# acoustic_1_1.net
KiCad netlist of a schematic drawn in EAGLE
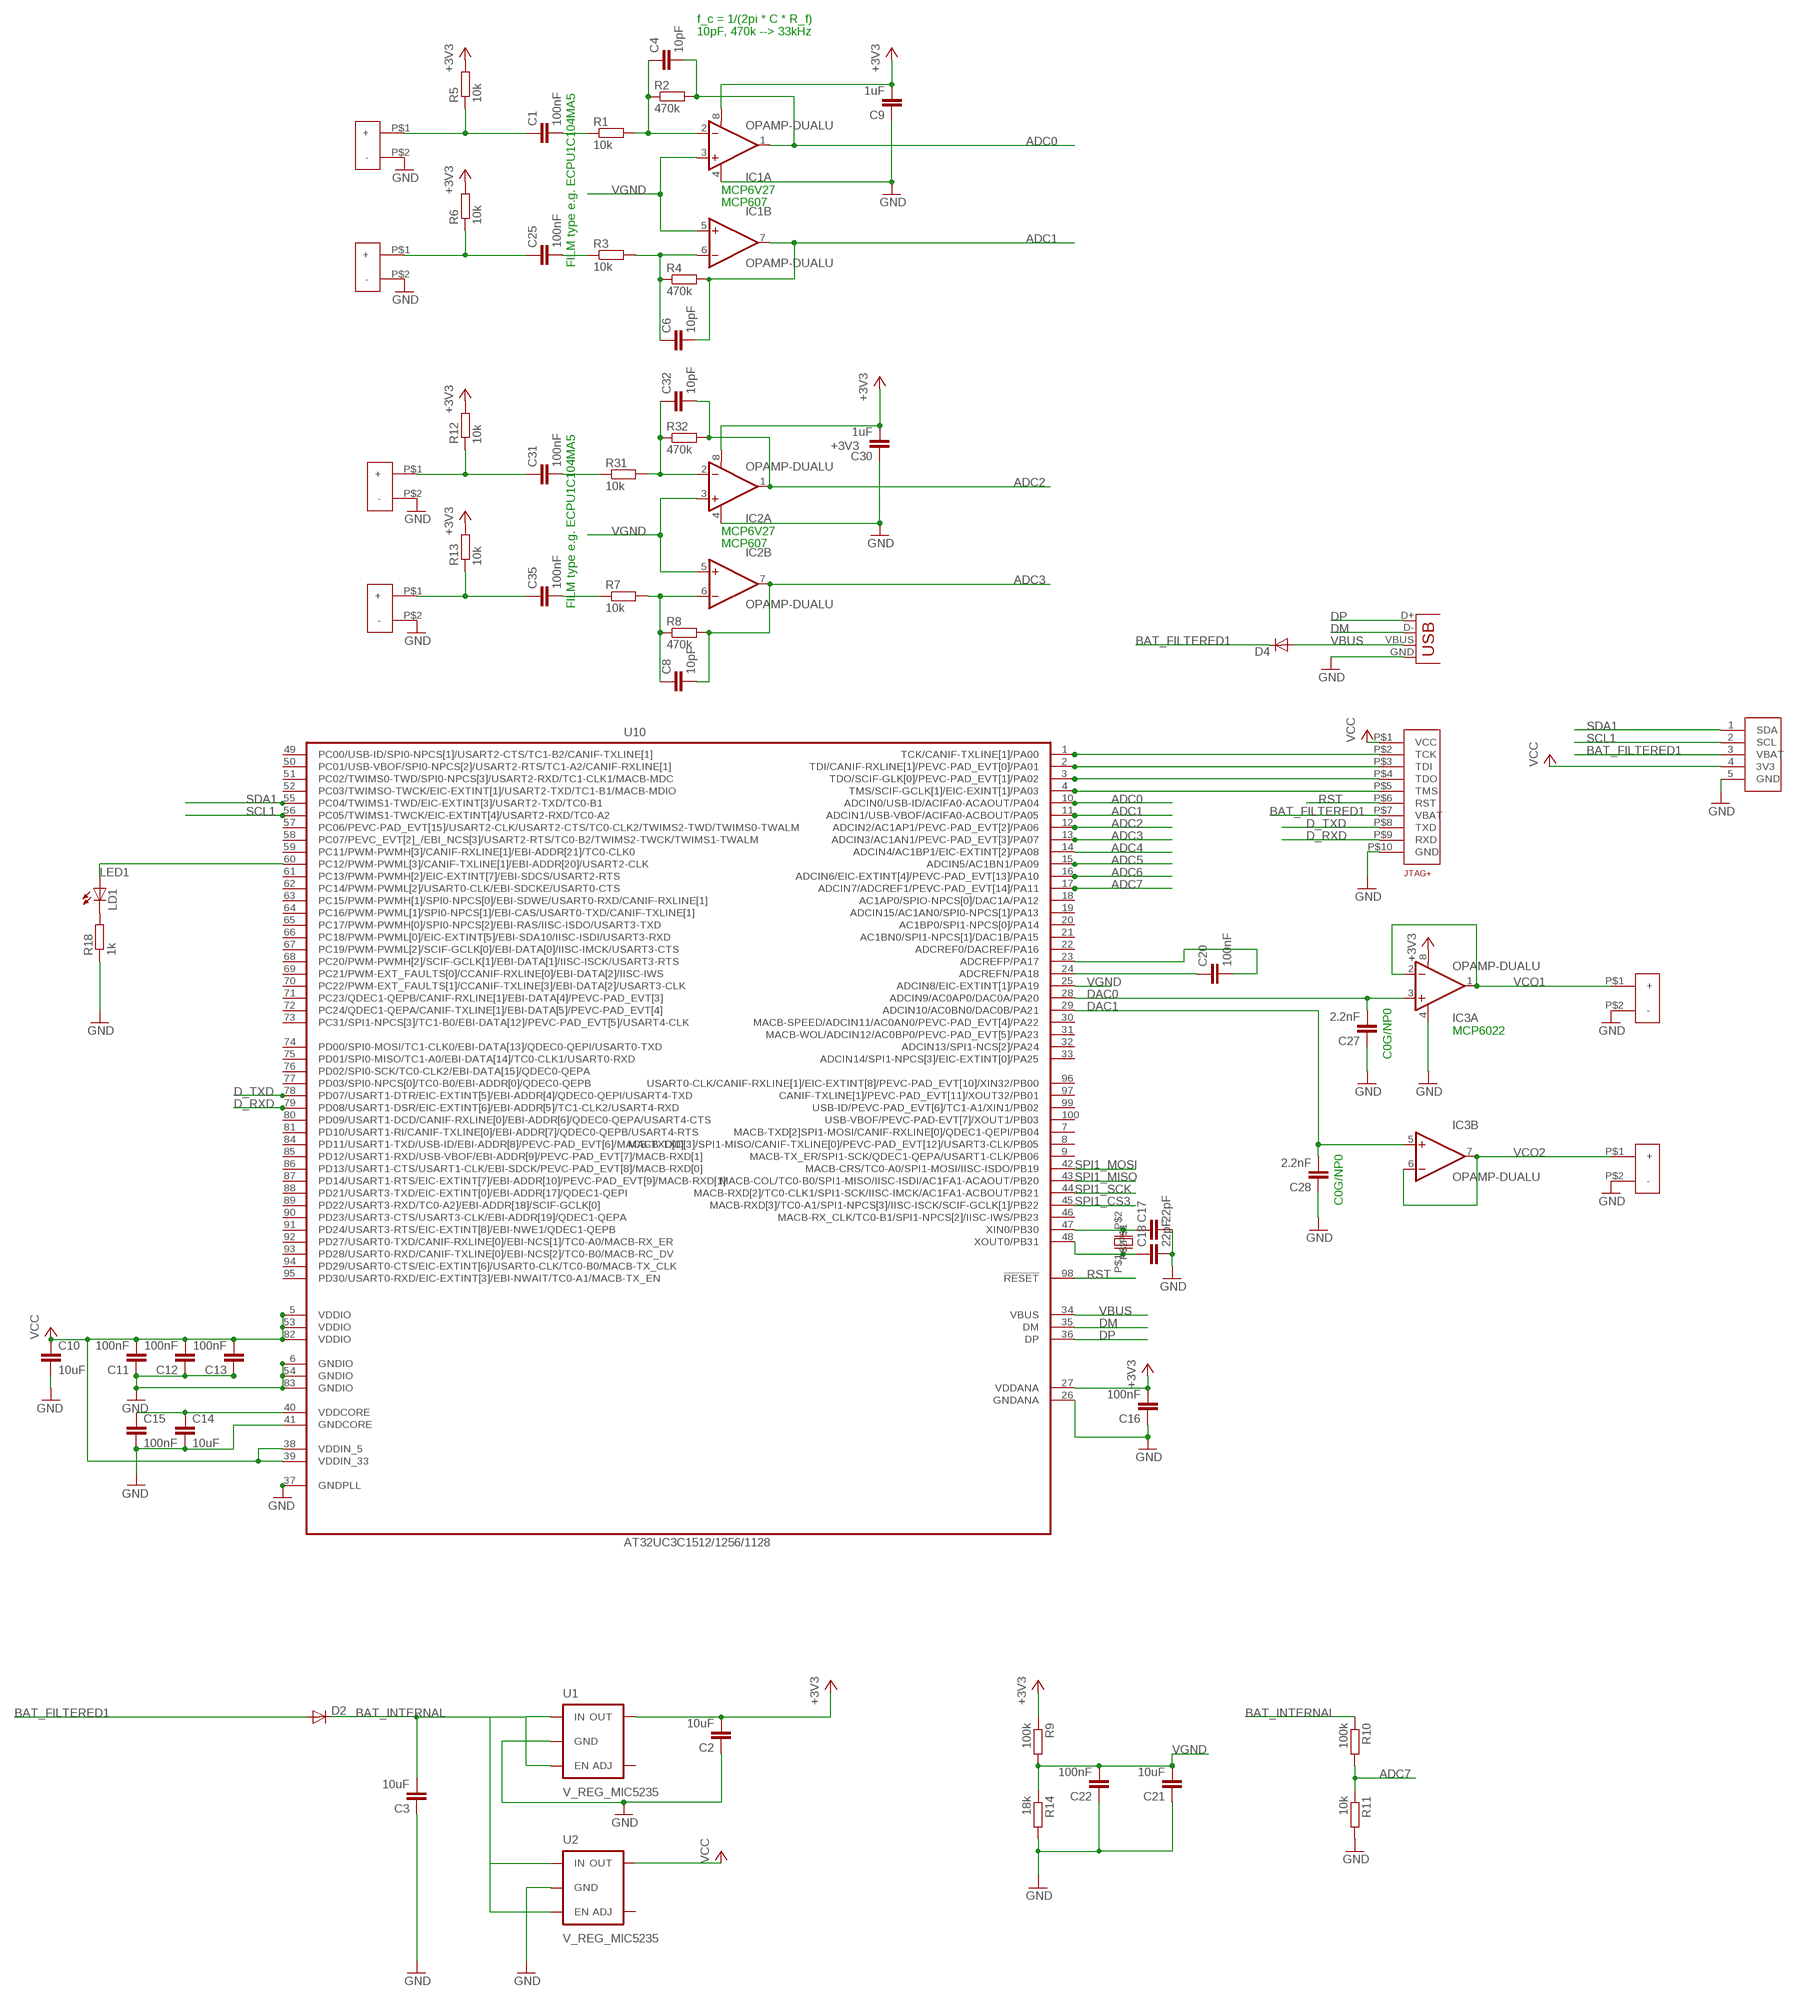
[diagram p0: schematic, sheet 1]

(export (version "E")
  (design (tool "Eeschema 10.0.6"))
  (components
    (comp (ref "BUS")
      (value "I2C_BUS_PICOVERTICAL")
      (footprint "eagle-import:MOLEX_CONNECTOR_5_PINS_VERTICAL")
      (libsource (lib "eagle-import") (part "I2C_BUS_PICOVERTICAL"))
    )
    (comp (ref "C1")
      (value "100nF")
      (footprint "eagle-import:C0805")
      (libsource (lib "eagle-import") (part "C-EUC0805"))
    )
    (comp (ref "C2")
      (value "10uF")
      (footprint "eagle-import:C0805")
      (libsource (lib "eagle-import") (part "C-EUC0805"))
    )
    (comp (ref "C3")
      (value "10uF")
      (footprint "eagle-import:C0805")
      (libsource (lib "eagle-import") (part "C-EUC0805"))
    )
    (comp (ref "C4")
      (value "10pF")
      (footprint "eagle-import:C0603")
      (libsource (lib "eagle-import") (part "C-EUC0603"))
    )
    (comp (ref "C6")
      (value "10pF")
      (footprint "eagle-import:C0603")
      (libsource (lib "eagle-import") (part "C-EUC0603"))
    )
    (comp (ref "C8")
      (value "10pF")
      (footprint "eagle-import:C0603")
      (libsource (lib "eagle-import") (part "C-EUC0603"))
    )
    (comp (ref "C9")
      (value "1uF")
      (footprint "eagle-import:C0805")
      (libsource (lib "eagle-import") (part "C-EUC0805"))
    )
    (comp (ref "C10")
      (value "10uF")
      (footprint "eagle-import:C0805")
      (libsource (lib "eagle-import") (part "C-EUC0805"))
    )
    (comp (ref "C11")
      (value "100nF")
      (footprint "eagle-import:C0603")
      (libsource (lib "eagle-import") (part "C-EUC0603"))
    )
    (comp (ref "C12")
      (value "100nF")
      (footprint "eagle-import:C0603")
      (libsource (lib "eagle-import") (part "C-EUC0603"))
    )
    (comp (ref "C13")
      (value "100nF")
      (footprint "eagle-import:C0603")
      (libsource (lib "eagle-import") (part "C-EUC0603"))
    )
    (comp (ref "C14")
      (value "10uF")
      (footprint "eagle-import:C0805")
      (libsource (lib "eagle-import") (part "C-EUC0805"))
    )
    (comp (ref "C15")
      (value "100nF")
      (footprint "eagle-import:C0603")
      (libsource (lib "eagle-import") (part "C-EUC0603"))
    )
    (comp (ref "C16")
      (value "100nF")
      (footprint "eagle-import:C0603")
      (libsource (lib "eagle-import") (part "C-EUC0603"))
    )
    (comp (ref "C17")
      (value "22pF")
      (footprint "eagle-import:C0402")
      (libsource (lib "eagle-import") (part "C-EUC0402"))
    )
    (comp (ref "C18")
      (value "22pF")
      (footprint "eagle-import:C0402")
      (libsource (lib "eagle-import") (part "C-EUC0402"))
    )
    (comp (ref "C20")
      (value "100nF")
      (footprint "eagle-import:C0603")
      (libsource (lib "eagle-import") (part "C-EUC0603"))
    )
    (comp (ref "C21")
      (value "10uF")
      (footprint "eagle-import:C0805")
      (libsource (lib "eagle-import") (part "C-EUC0805"))
    )
    (comp (ref "C22")
      (value "100nF")
      (footprint "eagle-import:C0603")
      (libsource (lib "eagle-import") (part "C-EUC0603"))
    )
    (comp (ref "C25")
      (value "100nF")
      (footprint "eagle-import:C0805")
      (libsource (lib "eagle-import") (part "C-EUC0805"))
    )
    (comp (ref "C27")
      (value "2.2nF")
      (footprint "eagle-import:C0805")
      (libsource (lib "eagle-import") (part "C-EUC0805"))
    )
    (comp (ref "C28")
      (value "2.2nF")
      (footprint "eagle-import:C0805")
      (libsource (lib "eagle-import") (part "C-EUC0805"))
    )
    (comp (ref "C30")
      (value "1uF")
      (footprint "eagle-import:C0805")
      (libsource (lib "eagle-import") (part "C-EUC0805"))
    )
    (comp (ref "C31")
      (value "100nF")
      (footprint "eagle-import:C0805")
      (libsource (lib "eagle-import") (part "C-EUC0805"))
    )
    (comp (ref "C32")
      (value "10pF")
      (footprint "eagle-import:C0603")
      (libsource (lib "eagle-import") (part "C-EUC0603"))
    )
    (comp (ref "C35")
      (value "100nF")
      (footprint "eagle-import:C0805")
      (libsource (lib "eagle-import") (part "C-EUC0805"))
    )
    (comp (ref "D2")
      (value "DIODESOD")
      (footprint "eagle-import:SOD-323")
      (libsource (lib "eagle-import") (part "DIODESOD"))
    )
    (comp (ref "D4")
      (value "DIODESOD")
      (footprint "eagle-import:SOD-323")
      (libsource (lib "eagle-import") (part "DIODESOD"))
    )
    (comp (ref "DEBUG")
      (value "AVR32_JTAG+SERIAL")
      (footprint "eagle-import:MOLEX_CONNECTOR_10PINS")
      (libsource (lib "eagle-import") (part "AVR32_JTAG+SERIAL"))
    )
    (comp (ref "IC1")
      (value "OPAMP-DUALU")
      (footprint "eagle-import:SO08")
      (libsource (lib "eagle-import") (part "OPAMP-DUALU"))
    )
    (comp (ref "IC2")
      (value "OPAMP-DUALU")
      (footprint "eagle-import:SO08")
      (libsource (lib "eagle-import") (part "OPAMP-DUALU"))
    )
    (comp (ref "IC3")
      (value "OPAMP-DUALU")
      (footprint "eagle-import:SO08")
      (libsource (lib "eagle-import") (part "OPAMP-DUALU"))
    )
    (comp (ref "LD1")
      (value "LEDCHIPLED_0805")
      (footprint "eagle-import:CHIPLED_0805")
      (libsource (lib "eagle-import") (part "LEDCHIPLED_0805"))
    )
    (comp (ref "M1")
      (value "POWER")
      (footprint "eagle-import:POWER")
      (libsource (lib "eagle-import") (part "POWER"))
    )
    (comp (ref "M2")
      (value "POWER")
      (footprint "eagle-import:POWER")
      (libsource (lib "eagle-import") (part "POWER"))
    )
    (comp (ref "M3")
      (value "POWER")
      (footprint "eagle-import:POWER")
      (libsource (lib "eagle-import") (part "POWER"))
    )
    (comp (ref "M4")
      (value "POWER")
      (footprint "eagle-import:POWER")
      (libsource (lib "eagle-import") (part "POWER"))
    )
    (comp (ref "O1")
      (value "POWER")
      (footprint "eagle-import:POWER")
      (libsource (lib "eagle-import") (part "POWER"))
    )
    (comp (ref "O2")
      (value "POWER")
      (footprint "eagle-import:POWER")
      (libsource (lib "eagle-import") (part "POWER"))
    )
    (comp (ref "R1")
      (value "10k")
      (footprint "eagle-import:R0603")
      (libsource (lib "eagle-import") (part "R-EU_R0603"))
    )
    (comp (ref "R2")
      (value "470k")
      (footprint "eagle-import:R0603")
      (libsource (lib "eagle-import") (part "R-EU_R0603"))
    )
    (comp (ref "R3")
      (value "10k")
      (footprint "eagle-import:R0603")
      (libsource (lib "eagle-import") (part "R-EU_R0603"))
    )
    (comp (ref "R4")
      (value "470k")
      (footprint "eagle-import:R0603")
      (libsource (lib "eagle-import") (part "R-EU_R0603"))
    )
    (comp (ref "R5")
      (value "10k")
      (footprint "eagle-import:R0603")
      (libsource (lib "eagle-import") (part "R-EU_R0603"))
    )
    (comp (ref "R6")
      (value "10k")
      (footprint "eagle-import:R0603")
      (libsource (lib "eagle-import") (part "R-EU_R0603"))
    )
    (comp (ref "R7")
      (value "10k")
      (footprint "eagle-import:R0603")
      (libsource (lib "eagle-import") (part "R-EU_R0603"))
    )
    (comp (ref "R8")
      (value "470k")
      (footprint "eagle-import:R0603")
      (libsource (lib "eagle-import") (part "R-EU_R0603"))
    )
    (comp (ref "R9")
      (value "100k")
      (footprint "eagle-import:R0603")
      (libsource (lib "eagle-import") (part "R-EU_R0603"))
    )
    (comp (ref "R10")
      (value "100k")
      (footprint "eagle-import:R0603")
      (libsource (lib "eagle-import") (part "R-EU_R0603"))
    )
    (comp (ref "R11")
      (value "10k")
      (footprint "eagle-import:R0603")
      (libsource (lib "eagle-import") (part "R-EU_R0603"))
    )
    (comp (ref "R12")
      (value "10k")
      (footprint "eagle-import:R0603")
      (libsource (lib "eagle-import") (part "R-EU_R0603"))
    )
    (comp (ref "R13")
      (value "10k")
      (footprint "eagle-import:R0603")
      (libsource (lib "eagle-import") (part "R-EU_R0603"))
    )
    (comp (ref "R14")
      (value "18k")
      (footprint "eagle-import:R0603")
      (libsource (lib "eagle-import") (part "R-EU_R0603"))
    )
    (comp (ref "R18")
      (value "1k")
      (footprint "eagle-import:R0603")
      (libsource (lib "eagle-import") (part "R-EU_R0603"))
    )
    (comp (ref "R31")
      (value "10k")
      (footprint "eagle-import:R0603")
      (libsource (lib "eagle-import") (part "R-EU_R0603"))
    )
    (comp (ref "R32")
      (value "470k")
      (footprint "eagle-import:R0603")
      (libsource (lib "eagle-import") (part "R-EU_R0603"))
    )
    (comp (ref "U$8")
      (value "CRYSTAL")
      (footprint "eagle-import:SMD_CRYSTAL_ABM")
      (libsource (lib "eagle-import") (part "CRYSTAL"))
    )
    (comp (ref "U1")
      (value "V_REG_MIC5235")
      (footprint "eagle-import:SOT23-5")
      (libsource (lib "eagle-import") (part "V_REG_MIC5235"))
    )
    (comp (ref "U2")
      (value "V_REG_MIC5235")
      (footprint "eagle-import:SOT23-5")
      (libsource (lib "eagle-import") (part "V_REG_MIC5235"))
    )
    (comp (ref "U10")
      (value "AT32UC3C1512/1256/1128")
      (footprint "eagle-import:TQFP100")
      (libsource (lib "eagle-import") (part "AT32UC3C1512/1256/1128"))
    )
    (comp (ref "X1")
      (value "USB-MICROB")
      (footprint "eagle-import:USB-MICROB")
      (libsource (lib "eagle-import") (part "USB-MICROB"))
    )
  )
  (nets
    (net (code "1") (name "+3V3") (class "Default")
      (node (ref "C16") (pin "2") (pinfunction "2_2") (pintype "passive"))
      (node (ref "C2") (pin "2") (pinfunction "2_2") (pintype "passive"))
      (node (ref "C30") (pin "2") (pinfunction "2_2") (pintype "passive"))
      (node (ref "C9") (pin "2") (pinfunction "2_2") (pintype "passive"))
      (node (ref "IC1") (pin "8") (pinfunction "V+_8") (pintype "power_in"))
      (node (ref "IC2") (pin "8") (pinfunction "V+_8") (pintype "power_in"))
      (node (ref "IC3") (pin "8") (pinfunction "V+_8") (pintype "power_in"))
      (node (ref "R12") (pin "2") (pinfunction "2_2") (pintype "passive"))
      (node (ref "R13") (pin "2") (pinfunction "2_2") (pintype "passive"))
      (node (ref "R5") (pin "2") (pinfunction "2_2") (pintype "passive"))
      (node (ref "R6") (pin "2") (pinfunction "2_2") (pintype "passive"))
      (node (ref "R9") (pin "1") (pinfunction "1_1") (pintype "passive"))
      (node (ref "U1") (pin "5") (pinfunction "OUT_5") (pintype "passive"))
      (node (ref "U10") (pin "27") (pinfunction "VDDANA_27") (pintype "power_in"))
    )
    (net (code "2") (name "/ADC0") (class "Default")
      (node (ref "C4") (pin "2") (pinfunction "2_2") (pintype "passive"))
      (node (ref "IC1") (pin "1") (pinfunction "OUT_1") (pintype "output"))
      (node (ref "R2") (pin "2") (pinfunction "2_2") (pintype "passive"))
      (node (ref "U10") (pin "10") (pinfunction "ADCIN0/USB-ID/ACIFA0-ACAOUT/PA04_10") (pintype "bidirectional"))
    )
    (net (code "3") (name "/ADC1") (class "Default")
      (node (ref "C6") (pin "2") (pinfunction "2_2") (pintype "passive"))
      (node (ref "IC1") (pin "7") (pinfunction "OUT_7") (pintype "output"))
      (node (ref "R4") (pin "2") (pinfunction "2_2") (pintype "passive"))
      (node (ref "U10") (pin "11") (pinfunction "ADCIN1/USB-VBOF/ACIFA0-ACBOUT/PA05_11") (pintype "bidirectional"))
    )
    (net (code "4") (name "/ADC2") (class "Default")
      (node (ref "C32") (pin "2") (pinfunction "2_2") (pintype "passive"))
      (node (ref "IC2") (pin "1") (pinfunction "OUT_1") (pintype "output"))
      (node (ref "R32") (pin "2") (pinfunction "2_2") (pintype "passive"))
      (node (ref "U10") (pin "12") (pinfunction "ADCIN2/AC1AP1/PEVC-PAD_EVT[2]/PA06_12") (pintype "bidirectional"))
    )
    (net (code "5") (name "/ADC3") (class "Default")
      (node (ref "C8") (pin "2") (pinfunction "2_2") (pintype "passive"))
      (node (ref "IC2") (pin "7") (pinfunction "OUT_7") (pintype "output"))
      (node (ref "R8") (pin "2") (pinfunction "2_2") (pintype "passive"))
      (node (ref "U10") (pin "13") (pinfunction "ADCIN3/AC1AN1/PEVC-PAD_EVT[3]/PA07_13") (pintype "bidirectional"))
    )
    (net (code "6") (name "/ADC4") (class "Default")
      (node (ref "U10") (pin "14") (pinfunction "ADCIN4/AC1BP1/EIC-EXTINT[2]/PA08_14") (pintype "bidirectional"))
    )
    (net (code "7") (name "/ADC5") (class "Default")
      (node (ref "U10") (pin "15") (pinfunction "ADCIN5/AC1BN1/PA09_15") (pintype "bidirectional"))
    )
    (net (code "8") (name "/ADC6") (class "Default")
      (node (ref "U10") (pin "16") (pinfunction "ADCIN6/EIC-EXTINT[4]/PEVC-PAD_EVT[13]/PA10_16") (pintype "bidirectional"))
    )
    (net (code "9") (name "/ADC7") (class "Default")
      (node (ref "R10") (pin "2") (pinfunction "2_2") (pintype "passive"))
      (node (ref "R11") (pin "1") (pinfunction "1_1") (pintype "passive"))
      (node (ref "U10") (pin "17") (pinfunction "ADCIN7/ADCREF1/PEVC-PAD_EVT[14]/PA11_17") (pintype "bidirectional"))
    )
    (net (code "10") (name "/BAT_FILTERED1") (class "Default")
      (node (ref "BUS") (pin "3") (pinfunction "VBAT_3") (pintype "bidirectional"))
      (node (ref "D2") (pin "2") (pinfunction "A_2") (pintype "passive"))
      (node (ref "D4") (pin "1") (pinfunction "C_1") (pintype "passive"))
      (node (ref "DEBUG") (pin "P$7") (pinfunction "VBAT_P$7") (pintype "bidirectional"))
    )
    (net (code "11") (name "/BAT_INTERNAL") (class "Default")
      (node (ref "C3") (pin "2") (pinfunction "2_2") (pintype "passive"))
      (node (ref "D2") (pin "1") (pinfunction "C_1") (pintype "passive"))
      (node (ref "R10") (pin "1") (pinfunction "1_1") (pintype "passive"))
      (node (ref "U1") (pin "1") (pinfunction "IN_1") (pintype "input"))
      (node (ref "U1") (pin "3") (pinfunction "EN_3") (pintype "input"))
      (node (ref "U2") (pin "1") (pinfunction "IN_1") (pintype "input"))
      (node (ref "U2") (pin "3") (pinfunction "EN_3") (pintype "input"))
    )
    (net (code "12") (name "/DAC0") (class "Default")
      (node (ref "C27") (pin "2") (pinfunction "2_2") (pintype "passive"))
      (node (ref "IC3") (pin "3") (pinfunction "+IN_3") (pintype "input"))
      (node (ref "U10") (pin "28") (pinfunction "ADCIN9/AC0AP0/DAC0A/PA20_28") (pintype "bidirectional"))
    )
    (net (code "13") (name "/DAC1") (class "Default")
      (node (ref "C28") (pin "2") (pinfunction "2_2") (pintype "passive"))
      (node (ref "IC3") (pin "5") (pinfunction "+IN_5") (pintype "input"))
      (node (ref "U10") (pin "29") (pinfunction "ADCIN10/AC0BN0/DAC0B/PA21_29") (pintype "bidirectional"))
    )
    (net (code "14") (name "/DM") (class "Default")
      (node (ref "U10") (pin "35") (pinfunction "DM_35") (pintype "bidirectional"))
      (node (ref "X1") (pin "D-") (pinfunction "D-_D-") (pintype "bidirectional"))
    )
    (net (code "15") (name "/DP") (class "Default")
      (node (ref "U10") (pin "36") (pinfunction "DP_36") (pintype "bidirectional"))
      (node (ref "X1") (pin "D+") (pinfunction "D+_D+") (pintype "bidirectional"))
    )
    (net (code "16") (name "/D_RXD") (class "Default")
      (node (ref "DEBUG") (pin "P$9") (pinfunction "RXD_P$9") (pintype "bidirectional"))
      (node (ref "U10") (pin "79") (pinfunction "PD08/USART1-DSR/EIC-EXTINT[6]/EBI-ADDR[5]/TC1-CLK2/USART4-RXD_79") (pintype "bidirectional"))
    )
    (net (code "17") (name "/D_TXD") (class "Default")
      (node (ref "DEBUG") (pin "P$8") (pinfunction "TXD_P$8") (pintype "bidirectional"))
      (node (ref "U10") (pin "78") (pinfunction "PD07/USART1-DTR/EIC-EXTINT[5]/EBI-ADDR[4]/QDEC0-QEPI/USART4-TXD_78") (pintype "bidirectional"))
    )
    (net (code "18") (name "/LED1") (class "Default")
      (node (ref "LD1") (pin "A") (pinfunction "A_A") (pintype "passive"))
      (node (ref "U10") (pin "60") (pinfunction "PC12/PWM-PWML[3]/CANIF-TXLINE[1]/EBI-ADDR[20]/USART2-CLK_60") (pintype "bidirectional"))
    )
    (net (code "19") (name "/RST") (class "Default")
      (node (ref "DEBUG") (pin "P$6") (pinfunction "RST_P$6") (pintype "bidirectional"))
      (node (ref "U10") (pin "98") (pinfunction "~{RESET}_98") (pintype "input"))
    )
    (net (code "20") (name "/SCL1") (class "Default")
      (node (ref "BUS") (pin "2") (pinfunction "SCL_2") (pintype "bidirectional"))
      (node (ref "U10") (pin "56") (pinfunction "PC05/TWIMS1-TWCK/EIC-EXTINT[4]/USART2-RXD/TC0-A2_56") (pintype "bidirectional"))
    )
    (net (code "21") (name "/SDA1") (class "Default")
      (node (ref "BUS") (pin "1") (pinfunction "SDA_1") (pintype "bidirectional"))
      (node (ref "U10") (pin "55") (pinfunction "PC04/TWIMS1-TWD/EIC-EXTINT[3]/USART2-TXD/TC0-B1_55") (pintype "bidirectional"))
    )
    (net (code "22") (name "/SPI1_CS3") (class "Default")
      (node (ref "U10") (pin "45") (pinfunction "MACB-RXD[3]/TC0-A1/SPI1-NPCS[3]/IISC-ISCK/SCIF-GCLK[1]/PB22_45") (pintype "bidirectional"))
    )
    (net (code "23") (name "/SPI1_MISO") (class "Default")
      (node (ref "U10") (pin "43") (pinfunction "MACB-COL/TC0-B0/SPI1-MISO/IISC-ISDI/AC1FA1-ACAOUT/PB20_43") (pintype "bidirectional"))
    )
    (net (code "24") (name "/SPI1_MOSI") (class "Default")
      (node (ref "U10") (pin "42") (pinfunction "MACB-CRS/TC0-A0/SPI1-MOSI/IISC-ISDO/PB19_42") (pintype "bidirectional"))
    )
    (net (code "25") (name "/SPI1_SCK") (class "Default")
      (node (ref "U10") (pin "44") (pinfunction "MACB-RXD[2]/TC0-CLK1/SPI1-SCK/IISC-IMCK/AC1FA1-ACBOUT/PB21_44") (pintype "bidirectional"))
    )
    (net (code "26") (name "/VBUS") (class "Default")
      (node (ref "D4") (pin "2") (pinfunction "A_2") (pintype "passive"))
      (node (ref "U10") (pin "34") (pinfunction "VBUS_34") (pintype "bidirectional"))
      (node (ref "X1") (pin "VBUS") (pinfunction "VBUS_VBUS") (pintype "bidirectional"))
    )
    (net (code "27") (name "/VCO1") (class "Default")
      (node (ref "IC3") (pin "1") (pinfunction "OUT_1") (pintype "output"))
      (node (ref "IC3") (pin "2") (pinfunction "-IN_2") (pintype "input"))
      (node (ref "O1") (pin "P$1") (pinfunction "+_P$1") (pintype "bidirectional"))
    )
    (net (code "28") (name "/VCO2") (class "Default")
      (node (ref "IC3") (pin "6") (pinfunction "-IN_6") (pintype "input"))
      (node (ref "IC3") (pin "7") (pinfunction "OUT_7") (pintype "output"))
      (node (ref "O2") (pin "P$1") (pinfunction "+_P$1") (pintype "bidirectional"))
    )
    (net (code "29") (name "/VGND") (class "Default")
      (node (ref "C21") (pin "2") (pinfunction "2_2") (pintype "passive"))
      (node (ref "C22") (pin "2") (pinfunction "2_2") (pintype "passive"))
      (node (ref "IC1") (pin "3") (pinfunction "+IN_3") (pintype "input"))
      (node (ref "IC1") (pin "5") (pinfunction "+IN_5") (pintype "input"))
      (node (ref "IC2") (pin "3") (pinfunction "+IN_3") (pintype "input"))
      (node (ref "IC2") (pin "5") (pinfunction "+IN_5") (pintype "input"))
      (node (ref "R14") (pin "1") (pinfunction "1_1") (pintype "passive"))
      (node (ref "R9") (pin "2") (pinfunction "2_2") (pintype "passive"))
      (node (ref "U10") (pin "25") (pinfunction "ADCIN8/EIC-EXTINT[1]/PA19_25") (pintype "bidirectional"))
    )
    (net (code "30") (name "GND") (class "Default")
      (node (ref "BUS") (pin "5") (pinfunction "GND_5") (pintype "bidirectional"))
      (node (ref "C10") (pin "2") (pinfunction "2_2") (pintype "passive"))
      (node (ref "C11") (pin "1") (pinfunction "1_1") (pintype "passive"))
      (node (ref "C12") (pin "1") (pinfunction "1_1") (pintype "passive"))
      (node (ref "C13") (pin "1") (pinfunction "1_1") (pintype "passive"))
      (node (ref "C14") (pin "2") (pinfunction "2_2") (pintype "passive"))
      (node (ref "C15") (pin "2") (pinfunction "2_2") (pintype "passive"))
      (node (ref "C16") (pin "1") (pinfunction "1_1") (pintype "passive"))
      (node (ref "C17") (pin "2") (pinfunction "2_2") (pintype "passive"))
      (node (ref "C18") (pin "2") (pinfunction "2_2") (pintype "passive"))
      (node (ref "C2") (pin "1") (pinfunction "1_1") (pintype "passive"))
      (node (ref "C21") (pin "1") (pinfunction "1_1") (pintype "passive"))
      (node (ref "C22") (pin "1") (pinfunction "1_1") (pintype "passive"))
      (node (ref "C27") (pin "1") (pinfunction "1_1") (pintype "passive"))
      (node (ref "C28") (pin "1") (pinfunction "1_1") (pintype "passive"))
      (node (ref "C3") (pin "1") (pinfunction "1_1") (pintype "passive"))
      (node (ref "C30") (pin "1") (pinfunction "1_1") (pintype "passive"))
      (node (ref "C9") (pin "1") (pinfunction "1_1") (pintype "passive"))
      (node (ref "DEBUG") (pin "P$10") (pinfunction "GND_P$10") (pintype "bidirectional"))
      (node (ref "IC1") (pin "4") (pinfunction "V-_4") (pintype "power_in"))
      (node (ref "IC2") (pin "4") (pinfunction "V-_4") (pintype "power_in"))
      (node (ref "IC3") (pin "4") (pinfunction "V-_4") (pintype "power_in"))
      (node (ref "M1") (pin "P$2") (pinfunction "-_P$2") (pintype "bidirectional"))
      (node (ref "M2") (pin "P$2") (pinfunction "-_P$2") (pintype "bidirectional"))
      (node (ref "M3") (pin "P$2") (pinfunction "-_P$2") (pintype "bidirectional"))
      (node (ref "M4") (pin "P$2") (pinfunction "-_P$2") (pintype "bidirectional"))
      (node (ref "O1") (pin "P$2") (pinfunction "-_P$2") (pintype "bidirectional"))
      (node (ref "O2") (pin "P$2") (pinfunction "-_P$2") (pintype "bidirectional"))
      (node (ref "R11") (pin "2") (pinfunction "2_2") (pintype "passive"))
      (node (ref "R14") (pin "2") (pinfunction "2_2") (pintype "passive"))
      (node (ref "R18") (pin "1") (pinfunction "1_1") (pintype "passive"))
      (node (ref "U1") (pin "2") (pinfunction "GND_2") (pintype "input"))
      (node (ref "U10") (pin "26") (pinfunction "GNDANA_26") (pintype "power_in"))
      (node (ref "U10") (pin "37") (pinfunction "GNDPLL_37") (pintype "power_in"))
      (node (ref "U10") (pin "41") (pinfunction "GNDCORE_41") (pintype "power_in"))
      (node (ref "U10") (pin "54") (pinfunction "GNDIO_54") (pintype "power_in"))
      (node (ref "U10") (pin "6") (pinfunction "GNDIO_6") (pintype "power_in"))
      (node (ref "U10") (pin "83") (pinfunction "GNDIO_83") (pintype "power_in"))
      (node (ref "U2") (pin "2") (pinfunction "GND_2") (pintype "input"))
      (node (ref "X1") (pin "GND") (pinfunction "GND_GND") (pintype "bidirectional"))
    )
    (net (code "31") (name "Net-(C1-Pad2)") (class "Default")
      (node (ref "C1") (pin "2") (pinfunction "2_2") (pintype "passive"))
      (node (ref "R1") (pin "1") (pinfunction "1_1") (pintype "passive"))
    )
    (net (code "32") (name "Net-(C25-Pad2)") (class "Default")
      (node (ref "C25") (pin "2") (pinfunction "2_2") (pintype "passive"))
      (node (ref "R3") (pin "1") (pinfunction "1_1") (pintype "passive"))
    )
    (net (code "33") (name "Net-(C31-Pad2)") (class "Default")
      (node (ref "C31") (pin "2") (pinfunction "2_2") (pintype "passive"))
      (node (ref "R31") (pin "1") (pinfunction "1_1") (pintype "passive"))
    )
    (net (code "34") (name "Net-(C35-Pad2)") (class "Default")
      (node (ref "C35") (pin "2") (pinfunction "2_2") (pintype "passive"))
      (node (ref "R7") (pin "1") (pinfunction "1_1") (pintype "passive"))
    )
    (net (code "35") (name "Net-(DEBUG-TCK)") (class "Default")
      (node (ref "DEBUG") (pin "P$2") (pinfunction "TCK_P$2") (pintype "bidirectional"))
      (node (ref "U10") (pin "1") (pinfunction "TCK/CANIF-TXLINE[1]/PA00_1") (pintype "bidirectional"))
    )
    (net (code "36") (name "Net-(DEBUG-TDI)") (class "Default")
      (node (ref "DEBUG") (pin "P$3") (pinfunction "TDI_P$3") (pintype "bidirectional"))
      (node (ref "U10") (pin "2") (pinfunction "TDI/CANIF-RXLINE[1]/PEVC-PAD_EVT[0]/PA01_2") (pintype "bidirectional"))
    )
    (net (code "37") (name "Net-(DEBUG-TDO)") (class "Default")
      (node (ref "DEBUG") (pin "P$4") (pinfunction "TDO_P$4") (pintype "bidirectional"))
      (node (ref "U10") (pin "3") (pinfunction "TDO/SCIF-GLK[0]/PEVC-PAD_EVT[1]/PA02_3") (pintype "bidirectional"))
    )
    (net (code "38") (name "Net-(DEBUG-TMS)") (class "Default")
      (node (ref "DEBUG") (pin "P$5") (pinfunction "TMS_P$5") (pintype "bidirectional"))
      (node (ref "U10") (pin "4") (pinfunction "TMS/SCIF-GCLK[1]/EIC-EXINT[1]/PA03_4") (pintype "bidirectional"))
    )
    (net (code "39") (name "Net-(IC1A--IN)") (class "Default")
      (node (ref "C4") (pin "1") (pinfunction "1_1") (pintype "passive"))
      (node (ref "IC1") (pin "2") (pinfunction "-IN_2") (pintype "input"))
      (node (ref "R1") (pin "2") (pinfunction "2_2") (pintype "passive"))
      (node (ref "R2") (pin "1") (pinfunction "1_1") (pintype "passive"))
    )
    (net (code "40") (name "Net-(IC1B--IN)") (class "Default")
      (node (ref "C6") (pin "1") (pinfunction "1_1") (pintype "passive"))
      (node (ref "IC1") (pin "6") (pinfunction "-IN_6") (pintype "input"))
      (node (ref "R3") (pin "2") (pinfunction "2_2") (pintype "passive"))
      (node (ref "R4") (pin "1") (pinfunction "1_1") (pintype "passive"))
    )
    (net (code "41") (name "Net-(IC2A--IN)") (class "Default")
      (node (ref "C32") (pin "1") (pinfunction "1_1") (pintype "passive"))
      (node (ref "IC2") (pin "2") (pinfunction "-IN_2") (pintype "input"))
      (node (ref "R31") (pin "2") (pinfunction "2_2") (pintype "passive"))
      (node (ref "R32") (pin "1") (pinfunction "1_1") (pintype "passive"))
    )
    (net (code "42") (name "Net-(IC2B--IN)") (class "Default")
      (node (ref "C8") (pin "1") (pinfunction "1_1") (pintype "passive"))
      (node (ref "IC2") (pin "6") (pinfunction "-IN_6") (pintype "input"))
      (node (ref "R7") (pin "2") (pinfunction "2_2") (pintype "passive"))
      (node (ref "R8") (pin "1") (pinfunction "1_1") (pintype "passive"))
    )
    (net (code "43") (name "Net-(LD1-PadC)") (class "Default")
      (node (ref "LD1") (pin "C") (pinfunction "C_C") (pintype "passive"))
      (node (ref "R18") (pin "2") (pinfunction "2_2") (pintype "passive"))
    )
    (net (code "44") (name "Net-(M1-+)") (class "Default")
      (node (ref "C1") (pin "1") (pinfunction "1_1") (pintype "passive"))
      (node (ref "M1") (pin "P$1") (pinfunction "+_P$1") (pintype "bidirectional"))
      (node (ref "R5") (pin "1") (pinfunction "1_1") (pintype "passive"))
    )
    (net (code "45") (name "Net-(M2-+)") (class "Default")
      (node (ref "C25") (pin "1") (pinfunction "1_1") (pintype "passive"))
      (node (ref "M2") (pin "P$1") (pinfunction "+_P$1") (pintype "bidirectional"))
      (node (ref "R6") (pin "1") (pinfunction "1_1") (pintype "passive"))
    )
    (net (code "46") (name "Net-(M3-+)") (class "Default")
      (node (ref "C31") (pin "1") (pinfunction "1_1") (pintype "passive"))
      (node (ref "M3") (pin "P$1") (pinfunction "+_P$1") (pintype "bidirectional"))
      (node (ref "R12") (pin "1") (pinfunction "1_1") (pintype "passive"))
    )
    (net (code "47") (name "Net-(M4-+)") (class "Default")
      (node (ref "C35") (pin "1") (pinfunction "1_1") (pintype "passive"))
      (node (ref "M4") (pin "P$1") (pinfunction "+_P$1") (pintype "bidirectional"))
      (node (ref "R13") (pin "1") (pinfunction "1_1") (pintype "passive"))
    )
    (net (code "48") (name "Net-(U10-ADCREFN{slash}PA18)") (class "Default")
      (node (ref "C20") (pin "1") (pinfunction "1_1") (pintype "passive"))
      (node (ref "U10") (pin "24") (pinfunction "ADCREFN/PA18_24") (pintype "bidirectional"))
    )
    (net (code "49") (name "Net-(U10-ADCREFP{slash}PA17)") (class "Default")
      (node (ref "C20") (pin "2") (pinfunction "2_2") (pintype "passive"))
      (node (ref "U10") (pin "23") (pinfunction "ADCREFP/PA17_23") (pintype "bidirectional"))
    )
    (net (code "50") (name "Net-(U10-VDDCORE)") (class "Default")
      (node (ref "C14") (pin "1") (pinfunction "1_1") (pintype "passive"))
      (node (ref "C15") (pin "1") (pinfunction "1_1") (pintype "passive"))
      (node (ref "U10") (pin "40") (pinfunction "VDDCORE_40") (pintype "power_in"))
    )
    (net (code "51") (name "Net-(U10-XIN0{slash}PB30)") (class "Default")
      (node (ref "C17") (pin "1") (pinfunction "1_1") (pintype "passive"))
      (node (ref "U$8") (pin "P$2") (pinfunction "P$2_P$2") (pintype "bidirectional"))
      (node (ref "U10") (pin "47") (pinfunction "XIN0/PB30_47") (pintype "bidirectional"))
    )
    (net (code "52") (name "Net-(U10-XOUT0{slash}PB31)") (class "Default")
      (node (ref "C18") (pin "1") (pinfunction "1_1") (pintype "passive"))
      (node (ref "U$8") (pin "P$1") (pinfunction "P$1_P$1") (pintype "bidirectional"))
      (node (ref "U10") (pin "48") (pinfunction "XOUT0/PB31_48") (pintype "bidirectional"))
    )
    (net (code "53") (name "VCC") (class "Default")
      (node (ref "BUS") (pin "4") (pinfunction "3V3_4") (pintype "bidirectional"))
      (node (ref "C10") (pin "1") (pinfunction "1_1") (pintype "passive"))
      (node (ref "C11") (pin "2") (pinfunction "2_2") (pintype "passive"))
      (node (ref "C12") (pin "2") (pinfunction "2_2") (pintype "passive"))
      (node (ref "C13") (pin "2") (pinfunction "2_2") (pintype "passive"))
      (node (ref "DEBUG") (pin "P$1") (pinfunction "VCC_P$1") (pintype "bidirectional"))
      (node (ref "U10") (pin "38") (pinfunction "VDDIN_5_38") (pintype "power_in"))
      (node (ref "U10") (pin "39") (pinfunction "VDDIN_33_39") (pintype "power_in"))
      (node (ref "U10") (pin "5") (pinfunction "VDDIO_5") (pintype "power_in"))
      (node (ref "U10") (pin "53") (pinfunction "VDDIO_53") (pintype "power_in"))
      (node (ref "U10") (pin "82") (pinfunction "VDDIO_82") (pintype "power_in"))
      (node (ref "U2") (pin "5") (pinfunction "OUT_5") (pintype "passive"))
    )
    (net (code "54") (name "unconnected-(U1-ADJ-Pad4)") (class "Default")
      (node (ref "U1") (pin "4") (pinfunction "ADJ_4") (pintype "input"))
    )
    (net (code "55") (name "unconnected-(U2-ADJ-Pad4)") (class "Default")
      (node (ref "U2") (pin "4") (pinfunction "ADJ_4") (pintype "input"))
    )
    (net (code "56") (name "unconnected-(U10-AC1AP0{slash}SPIO-NPCS[0]{slash}DAC1A{slash}PA12-Pad18)") (class "Default")
      (node (ref "U10") (pin "18") (pinfunction "AC1AP0/SPIO-NPCS[0]/DAC1A/PA12_18") (pintype "bidirectional"))
    )
    (net (code "57") (name "unconnected-(U10-AC1BN0{slash}SPI1-NPCS[1]{slash}DAC1B{slash}PA15-Pad21)") (class "Default")
      (node (ref "U10") (pin "21") (pinfunction "AC1BN0/SPI1-NPCS[1]/DAC1B/PA15_21") (pintype "bidirectional"))
    )
    (net (code "58") (name "unconnected-(U10-AC1BP0{slash}SPI1-NPCS[0]{slash}PA14-Pad20)") (class "Default")
      (node (ref "U10") (pin "20") (pinfunction "AC1BP0/SPI1-NPCS[0]/PA14_20") (pintype "bidirectional"))
    )
    (net (code "59") (name "unconnected-(U10-ADCIN13{slash}SPI1-NCS[2]{slash}PA24-Pad32)") (class "Default")
      (node (ref "U10") (pin "32") (pinfunction "ADCIN13/SPI1-NCS[2]/PA24_32") (pintype "bidirectional"))
    )
    (net (code "60") (name "unconnected-(U10-ADCIN14{slash}SPI1-NPCS[3]{slash}EIC-EXTINT[0]{slash}PA25-Pad33)") (class "Default")
      (node (ref "U10") (pin "33") (pinfunction "ADCIN14/SPI1-NPCS[3]/EIC-EXTINT[0]/PA25_33") (pintype "bidirectional"))
    )
    (net (code "61") (name "unconnected-(U10-ADCIN15{slash}AC1AN0{slash}SPI0-NPCS[1]{slash}PA13-Pad19)") (class "Default")
      (node (ref "U10") (pin "19") (pinfunction "ADCIN15/AC1AN0/SPI0-NPCS[1]/PA13_19") (pintype "bidirectional"))
    )
    (net (code "62") (name "unconnected-(U10-ADCREF0{slash}DACREF{slash}PA16-Pad22)") (class "Default")
      (node (ref "U10") (pin "22") (pinfunction "ADCREF0/DACREF/PA16_22") (pintype "bidirectional"))
    )
    (net (code "63") (name "unconnected-(U10-CANIF-TXLINE[1]{slash}PEVC-PAD_EVT[11]{slash}XOUT32{slash}PB01-Pad97)") (class "Default")
      (node (ref "U10") (pin "97") (pinfunction "CANIF-TXLINE[1]/PEVC-PAD_EVT[11]/XOUT32/PB01_97") (pintype "bidirectional"))
    )
    (net (code "64") (name "unconnected-(U10-MACB-RX_CLK{slash}TC0-B1{slash}SPI1-NPCS[2]{slash}IISC-IWS{slash}PB23-Pad46)") (class "Default")
      (node (ref "U10") (pin "46") (pinfunction "MACB-RX_CLK/TC0-B1/SPI1-NPCS[2]/IISC-IWS/PB23_46") (pintype "bidirectional"))
    )
    (net (code "65") (name "unconnected-(U10-MACB-SPEED{slash}ADCIN11{slash}AC0AN0{slash}PEVC-PAD_EVT[4]{slash}PA22-Pad30)") (class "Default")
      (node (ref "U10") (pin "30") (pinfunction "MACB-SPEED/ADCIN11/AC0AN0/PEVC-PAD_EVT[4]/PA22_30") (pintype "bidirectional"))
    )
    (net (code "66") (name "unconnected-(U10-MACB-TXD[2]SPI1-MOSI{slash}CANIF-RXLINE[0]{slash}QDEC1-QEPI{slash}PB04-Pad7)") (class "Default")
      (node (ref "U10") (pin "7") (pinfunction "MACB-TXD[2]SPI1-MOSI/CANIF-RXLINE[0]/QDEC1-QEPI/PB04_7") (pintype "bidirectional"))
    )
    (net (code "67") (name "unconnected-(U10-MACB-TXD[3]{slash}SPI1-MISO{slash}CANIF-TXLINE[0]{slash}PEVC-PAD_EVT[12]{slash}USART3-CLK{slash}PB05-Pad8)") (class "Default")
      (node (ref "U10") (pin "8") (pinfunction "MACB-TXD[3]/SPI1-MISO/CANIF-TXLINE[0]/PEVC-PAD_EVT[12]/USART3-CLK/PB05_8") (pintype "bidirectional"))
    )
    (net (code "68") (name "unconnected-(U10-MACB-TX_ER{slash}SPI1-SCK{slash}QDEC1-QEPA{slash}USART1-CLK{slash}PB06-Pad9)") (class "Default")
      (node (ref "U10") (pin "9") (pinfunction "MACB-TX_ER/SPI1-SCK/QDEC1-QEPA/USART1-CLK/PB06_9") (pintype "bidirectional"))
    )
    (net (code "69") (name "unconnected-(U10-MACB-WOL{slash}ADCIN12{slash}AC0BP0{slash}PEVC-PAD_EVT[5]{slash}PA23-Pad31)") (class "Default")
      (node (ref "U10") (pin "31") (pinfunction "MACB-WOL/ADCIN12/AC0BP0/PEVC-PAD_EVT[5]/PA23_31") (pintype "bidirectional"))
    )
    (net (code "70") (name "unconnected-(U10-PC00{slash}USB-ID{slash}SPI0-NPCS[1]{slash}USART2-CTS{slash}TC1-B2{slash}CANIF-TXLINE[1]-Pad49)") (class "Default")
      (node (ref "U10") (pin "49") (pinfunction "PC00/USB-ID/SPI0-NPCS[1]/USART2-CTS/TC1-B2/CANIF-TXLINE[1]_49") (pintype "bidirectional"))
    )
    (net (code "71") (name "unconnected-(U10-PC01{slash}USB-VBOF{slash}SPI0-NPCS[2]{slash}USART2-RTS{slash}TC1-A2{slash}CANIF-RXLINE[1]-Pad50)") (class "Default")
      (node (ref "U10") (pin "50") (pinfunction "PC01/USB-VBOF/SPI0-NPCS[2]/USART2-RTS/TC1-A2/CANIF-RXLINE[1]_50") (pintype "bidirectional"))
    )
    (net (code "72") (name "unconnected-(U10-PC02{slash}TWIMS0-TWD{slash}SPI0-NPCS[3]{slash}USART2-RXD{slash}TC1-CLK1{slash}MACB-MDC-Pad51)") (class "Default")
      (node (ref "U10") (pin "51") (pinfunction "PC02/TWIMS0-TWD/SPI0-NPCS[3]/USART2-RXD/TC1-CLK1/MACB-MDC_51") (pintype "bidirectional"))
    )
    (net (code "73") (name "unconnected-(U10-PC03{slash}TWIMSO-TWCK{slash}EIC-EXTINT[1]{slash}USART2-TXD{slash}TC1-B1{slash}MACB-MDIO-Pad52)") (class "Default")
      (node (ref "U10") (pin "52") (pinfunction "PC03/TWIMSO-TWCK/EIC-EXTINT[1]/USART2-TXD/TC1-B1/MACB-MDIO_52") (pintype "bidirectional"))
    )
    (net (code "74") (name "unconnected-(U10-PC06{slash}PEVC-PAD_EVT[15]{slash}USART2-CLK{slash}USART2-CTS{slash}TC0-CLK2{slash}TWIMS2-TWD{slash}TWIMS0-TWALM-Pad57)") (class "Default")
      (node (ref "U10") (pin "57") (pinfunction "PC06/PEVC-PAD_EVT[15]/USART2-CLK/USART2-CTS/TC0-CLK2/TWIMS2-TWD/TWIMS0-TWALM_57") (pintype "bidirectional"))
    )
    (net (code "75") (name "unconnected-(U10-PC07{slash}PEVC_EVT[2]_{slash}EBI_NCS[3]{slash}USART2-RTS{slash}TC0-B2{slash}TWIMS2-TWCK{slash}TWIMS1-TWALM-Pad58)") (class "Default")
      (node (ref "U10") (pin "58") (pinfunction "PC07/PEVC_EVT[2]_/EBI_NCS[3]/USART2-RTS/TC0-B2/TWIMS2-TWCK/TWIMS1-TWALM_58") (pintype "bidirectional"))
    )
    (net (code "76") (name "unconnected-(U10-PC11{slash}PWM-PWMH[3]{slash}CANIF-RXLINE[1]{slash}EBI-ADDR[21]{slash}TC0-CLK0-Pad59)") (class "Default")
      (node (ref "U10") (pin "59") (pinfunction "PC11/PWM-PWMH[3]/CANIF-RXLINE[1]/EBI-ADDR[21]/TC0-CLK0_59") (pintype "bidirectional"))
    )
    (net (code "77") (name "unconnected-(U10-PC13{slash}PWM-PWMH[2]{slash}EIC-EXTINT[7]{slash}EBI-SDCS{slash}USART2-RTS-Pad61)") (class "Default")
      (node (ref "U10") (pin "61") (pinfunction "PC13/PWM-PWMH[2]/EIC-EXTINT[7]/EBI-SDCS/USART2-RTS_61") (pintype "bidirectional"))
    )
    (net (code "78") (name "unconnected-(U10-PC14{slash}PWM-PWML[2]{slash}USART0-CLK{slash}EBI-SDCKE{slash}USART0-CTS-Pad62)") (class "Default")
      (node (ref "U10") (pin "62") (pinfunction "PC14/PWM-PWML[2]/USART0-CLK/EBI-SDCKE/USART0-CTS_62") (pintype "bidirectional"))
    )
    (net (code "79") (name "unconnected-(U10-PC15{slash}PWM-PWMH[1]{slash}SPI0-NPCS[0]{slash}EBI-SDWE{slash}USART0-RXD{slash}CANIF-RXLINE[1]-Pad63)") (class "Default")
      (node (ref "U10") (pin "63") (pinfunction "PC15/PWM-PWMH[1]/SPI0-NPCS[0]/EBI-SDWE/USART0-RXD/CANIF-RXLINE[1]_63") (pintype "bidirectional"))
    )
    (net (code "80") (name "unconnected-(U10-PC16{slash}PWM-PWML[1]{slash}SPI0-NPCS[1]{slash}EBI-CAS{slash}USART0-TXD{slash}CANIF-TXLINE[1]-Pad64)") (class "Default")
      (node (ref "U10") (pin "64") (pinfunction "PC16/PWM-PWML[1]/SPI0-NPCS[1]/EBI-CAS/USART0-TXD/CANIF-TXLINE[1]_64") (pintype "bidirectional"))
    )
    (net (code "81") (name "unconnected-(U10-PC17{slash}PWM-PWMH[0]{slash}SPI0-NPCS[2]{slash}EBI-RAS{slash}IISC-ISDO{slash}USART3-TXD-Pad65)") (class "Default")
      (node (ref "U10") (pin "65") (pinfunction "PC17/PWM-PWMH[0]/SPI0-NPCS[2]/EBI-RAS/IISC-ISDO/USART3-TXD_65") (pintype "bidirectional"))
    )
    (net (code "82") (name "unconnected-(U10-PC18{slash}PWM-PWML[0]{slash}EIC-EXTINT[5]{slash}EBI-SDA10{slash}IISC-ISDI{slash}USART3-RXD-Pad66)") (class "Default")
      (node (ref "U10") (pin "66") (pinfunction "PC18/PWM-PWML[0]/EIC-EXTINT[5]/EBI-SDA10/IISC-ISDI/USART3-RXD_66") (pintype "bidirectional"))
    )
    (net (code "83") (name "unconnected-(U10-PC19{slash}PWM-PWML[2]{slash}SCIF-GCLK[0]{slash}EBI-DATA[0]{slash}IISC-IMCK{slash}USART3-CTS-Pad67)") (class "Default")
      (node (ref "U10") (pin "67") (pinfunction "PC19/PWM-PWML[2]/SCIF-GCLK[0]/EBI-DATA[0]/IISC-IMCK/USART3-CTS_67") (pintype "bidirectional"))
    )
    (net (code "84") (name "unconnected-(U10-PC20{slash}PWM-PWMH[2]{slash}SCIF-GCLK[1]{slash}EBI-DATA[1]{slash}IISC-ISCK{slash}USART3-RTS-Pad68)") (class "Default")
      (node (ref "U10") (pin "68") (pinfunction "PC20/PWM-PWMH[2]/SCIF-GCLK[1]/EBI-DATA[1]/IISC-ISCK/USART3-RTS_68") (pintype "bidirectional"))
    )
    (net (code "85") (name "unconnected-(U10-PC21{slash}PWM-EXT_FAULTS[0]{slash}CCANIF-RXLINE[0]{slash}EBI-DATA[2]{slash}IISC-IWS-Pad69)") (class "Default")
      (node (ref "U10") (pin "69") (pinfunction "PC21/PWM-EXT_FAULTS[0]/CCANIF-RXLINE[0]/EBI-DATA[2]/IISC-IWS_69") (pintype "bidirectional"))
    )
    (net (code "86") (name "unconnected-(U10-PC22{slash}PWM-EXT_FAULTS[1]{slash}CCANIF-TXLINE[3]{slash}EBI-DATA[2]{slash}USART3-CLK-Pad70)") (class "Default")
      (node (ref "U10") (pin "70") (pinfunction "PC22/PWM-EXT_FAULTS[1]/CCANIF-TXLINE[3]/EBI-DATA[2]/USART3-CLK_70") (pintype "bidirectional"))
    )
    (net (code "87") (name "unconnected-(U10-PC23{slash}QDEC1-QEPB{slash}CANIF-RXLINE[1]{slash}EBI-DATA[4]{slash}PEVC-PAD_EVT[3]-Pad71)") (class "Default")
      (node (ref "U10") (pin "71") (pinfunction "PC23/QDEC1-QEPB/CANIF-RXLINE[1]/EBI-DATA[4]/PEVC-PAD_EVT[3]_71") (pintype "bidirectional"))
    )
    (net (code "88") (name "unconnected-(U10-PC24{slash}QDEC1-QEPA{slash}CANIF-TXLINE[1]{slash}EBI-DATA[5]{slash}PEVC-PAD_EVT[4]-Pad72)") (class "Default")
      (node (ref "U10") (pin "72") (pinfunction "PC24/QDEC1-QEPA/CANIF-TXLINE[1]/EBI-DATA[5]/PEVC-PAD_EVT[4]_72") (pintype "bidirectional"))
    )
    (net (code "89") (name "unconnected-(U10-PC31{slash}SPI1-NPCS[3]{slash}TC1-B0{slash}EBI-DATA[12]{slash}PEVC-PAD_EVT[5]{slash}USART4-CLK-Pad73)") (class "Default")
      (node (ref "U10") (pin "73") (pinfunction "PC31/SPI1-NPCS[3]/TC1-B0/EBI-DATA[12]/PEVC-PAD_EVT[5]/USART4-CLK_73") (pintype "bidirectional"))
    )
    (net (code "90") (name "unconnected-(U10-PD00{slash}SPI0-MOSI{slash}TC1-CLK0{slash}EBI-DATA[13]{slash}QDEC0-QEPI{slash}USART0-TXD-Pad74)") (class "Default")
      (node (ref "U10") (pin "74") (pinfunction "PD00/SPI0-MOSI/TC1-CLK0/EBI-DATA[13]/QDEC0-QEPI/USART0-TXD_74") (pintype "bidirectional"))
    )
    (net (code "91") (name "unconnected-(U10-PD01{slash}SPI0-MISO{slash}TC1-A0{slash}EBI-DATA[14]{slash}TC0-CLK1{slash}USART0-RXD-Pad75)") (class "Default")
      (node (ref "U10") (pin "75") (pinfunction "PD01/SPI0-MISO/TC1-A0/EBI-DATA[14]/TC0-CLK1/USART0-RXD_75") (pintype "bidirectional"))
    )
    (net (code "92") (name "unconnected-(U10-PD02{slash}SPI0-SCK{slash}TC0-CLK2{slash}EBI-DATA[15]{slash}QDEC0-QEPA-Pad76)") (class "Default")
      (node (ref "U10") (pin "76") (pinfunction "PD02/SPI0-SCK/TC0-CLK2/EBI-DATA[15]/QDEC0-QEPA_76") (pintype "bidirectional"))
    )
    (net (code "93") (name "unconnected-(U10-PD03{slash}SPI0-NPCS[0]{slash}TC0-B0{slash}EBI-ADDR[0]{slash}QDEC0-QEPB-Pad77)") (class "Default")
      (node (ref "U10") (pin "77") (pinfunction "PD03/SPI0-NPCS[0]/TC0-B0/EBI-ADDR[0]/QDEC0-QEPB_77") (pintype "bidirectional"))
    )
    (net (code "94") (name "unconnected-(U10-PD09{slash}USART1-DCD{slash}CANIF-RXLINE[0]{slash}EBI-ADDR[6]{slash}QDEC0-QEPA{slash}USART4-CTS-Pad80)") (class "Default")
      (node (ref "U10") (pin "80") (pinfunction "PD09/USART1-DCD/CANIF-RXLINE[0]/EBI-ADDR[6]/QDEC0-QEPA/USART4-CTS_80") (pintype "bidirectional"))
    )
    (net (code "95") (name "unconnected-(U10-PD10{slash}USART1-RI{slash}CANIF-TXLINE[0]{slash}EBI-ADDR[7]{slash}QDEC0-QEPB{slash}USART4-RTS-Pad81)") (class "Default")
      (node (ref "U10") (pin "81") (pinfunction "PD10/USART1-RI/CANIF-TXLINE[0]/EBI-ADDR[7]/QDEC0-QEPB/USART4-RTS_81") (pintype "bidirectional"))
    )
    (net (code "96") (name "unconnected-(U10-PD11{slash}USART1-TXD{slash}USB-ID{slash}EBI-ADDR[8]{slash}PEVC-PAD_EVT[6]{slash}MACB-TXD[0]-Pad84)") (class "Default")
      (node (ref "U10") (pin "84") (pinfunction "PD11/USART1-TXD/USB-ID/EBI-ADDR[8]/PEVC-PAD_EVT[6]/MACB-TXD[0]_84") (pintype "bidirectional"))
    )
    (net (code "97") (name "unconnected-(U10-PD12{slash}USART1-RXD{slash}USB-VBOF{slash}EBI-ADDR[9]{slash}PEVC-PAD_EVT[7]{slash}MACB-RXD[1]-Pad85)") (class "Default")
      (node (ref "U10") (pin "85") (pinfunction "PD12/USART1-RXD/USB-VBOF/EBI-ADDR[9]/PEVC-PAD_EVT[7]/MACB-RXD[1]_85") (pintype "bidirectional"))
    )
    (net (code "98") (name "unconnected-(U10-PD13{slash}USART1-CTS{slash}USART1-CLK{slash}EBI-SDCK{slash}PEVC-PAD_EVT[8]{slash}MACB-RXD[0]-Pad86)") (class "Default")
      (node (ref "U10") (pin "86") (pinfunction "PD13/USART1-CTS/USART1-CLK/EBI-SDCK/PEVC-PAD_EVT[8]/MACB-RXD[0]_86") (pintype "bidirectional"))
    )
    (net (code "99") (name "unconnected-(U10-PD14{slash}USART1-RTS{slash}EIC-EXTINT[7]{slash}EBI-ADDR[10]{slash}PEVC-PAD_EVT[9]{slash}MACB-RXD[1]-Pad87)") (class "Default")
      (node (ref "U10") (pin "87") (pinfunction "PD14/USART1-RTS/EIC-EXTINT[7]/EBI-ADDR[10]/PEVC-PAD_EVT[9]/MACB-RXD[1]_87") (pintype "bidirectional"))
    )
    (net (code "100") (name "unconnected-(U10-PD21{slash}USART3-TXD{slash}EIC-EXTINT[0]{slash}EBI-ADDR[17]{slash}QDEC1-QEPI-Pad88)") (class "Default")
      (node (ref "U10") (pin "88") (pinfunction "PD21/USART3-TXD/EIC-EXTINT[0]/EBI-ADDR[17]/QDEC1-QEPI_88") (pintype "bidirectional"))
    )
    (net (code "101") (name "unconnected-(U10-PD22{slash}USART3-RXD{slash}TC0-A2]{slash}EBI-ADDR[18]{slash}SCIF-GCLK[0]-Pad89)") (class "Default")
      (node (ref "U10") (pin "89") (pinfunction "PD22/USART3-RXD/TC0-A2]/EBI-ADDR[18]/SCIF-GCLK[0]_89") (pintype "bidirectional"))
    )
    (net (code "102") (name "unconnected-(U10-PD23{slash}USART3-CTS{slash}USART3-CLK{slash}EBI-ADDR[19]{slash}QDEC1-QEPA-Pad90)") (class "Default")
      (node (ref "U10") (pin "90") (pinfunction "PD23/USART3-CTS/USART3-CLK/EBI-ADDR[19]/QDEC1-QEPA_90") (pintype "bidirectional"))
    )
    (net (code "103") (name "unconnected-(U10-PD24{slash}USART3-RTS{slash}EIC-EXTINT[8]{slash}EBI-NWE1{slash}QDEC1-QEPB-Pad91)") (class "Default")
      (node (ref "U10") (pin "91") (pinfunction "PD24/USART3-RTS/EIC-EXTINT[8]/EBI-NWE1/QDEC1-QEPB_91") (pintype "bidirectional"))
    )
    (net (code "104") (name "unconnected-(U10-PD27{slash}USART0-TXD{slash}CANIF-RXLINE[0]{slash}EBI-NCS[1]{slash}TC0-A0{slash}MACB-RX_ER-Pad92)") (class "Default")
      (node (ref "U10") (pin "92") (pinfunction "PD27/USART0-TXD/CANIF-RXLINE[0]/EBI-NCS[1]/TC0-A0/MACB-RX_ER_92") (pintype "bidirectional"))
    )
    (net (code "105") (name "unconnected-(U10-PD28{slash}USART0-RXD{slash}CANIF-TXLINE[0]{slash}EBI-NCS[2]{slash}TC0-B0{slash}MACB-RC_DV-Pad93)") (class "Default")
      (node (ref "U10") (pin "93") (pinfunction "PD28/USART0-RXD/CANIF-TXLINE[0]/EBI-NCS[2]/TC0-B0/MACB-RC_DV_93") (pintype "bidirectional"))
    )
    (net (code "106") (name "unconnected-(U10-PD29{slash}USART0-CTS{slash}EIC-EXTINT[6]{slash}USART0-CLK{slash}TC0-B0{slash}MACB-TX_CLK-Pad94)") (class "Default")
      (node (ref "U10") (pin "94") (pinfunction "PD29/USART0-CTS/EIC-EXTINT[6]/USART0-CLK/TC0-B0/MACB-TX_CLK_94") (pintype "bidirectional"))
    )
    (net (code "107") (name "unconnected-(U10-PD30{slash}USART0-RXD{slash}EIC-EXTINT[3]{slash}EBI-NWAIT{slash}TC0-A1{slash}MACB-TX_EN-Pad95)") (class "Default")
      (node (ref "U10") (pin "95") (pinfunction "PD30/USART0-RXD/EIC-EXTINT[3]/EBI-NWAIT/TC0-A1/MACB-TX_EN_95") (pintype "bidirectional"))
    )
    (net (code "108") (name "unconnected-(U10-USART0-CLK{slash}CANIF-RXLINE[1]{slash}EIC-EXTINT[8]{slash}PEVC-PAD_EVT[10]{slash}XIN32{slash}PB00-Pad96)") (class "Default")
      (node (ref "U10") (pin "96") (pinfunction "USART0-CLK/CANIF-RXLINE[1]/EIC-EXTINT[8]/PEVC-PAD_EVT[10]/XIN32/PB00_96") (pintype "bidirectional"))
    )
    (net (code "109") (name "unconnected-(U10-USB-ID{slash}PEVC-PAD_EVT[6]{slash}TC1-A1{slash}XIN1{slash}PB02-Pad99)") (class "Default")
      (node (ref "U10") (pin "99") (pinfunction "USB-ID/PEVC-PAD_EVT[6]/TC1-A1/XIN1/PB02_99") (pintype "bidirectional"))
    )
    (net (code "110") (name "unconnected-(U10-USB-VBOF{slash}PEVC-PAD-EVT[7]{slash}XOUT1{slash}PB03-Pad100)") (class "Default")
      (node (ref "U10") (pin "100") (pinfunction "USB-VBOF/PEVC-PAD-EVT[7]/XOUT1/PB03_100") (pintype "bidirectional"))
    )
  )
)
